# power_board.net
KiCad netlist of a schematic drawn in Altium Designer
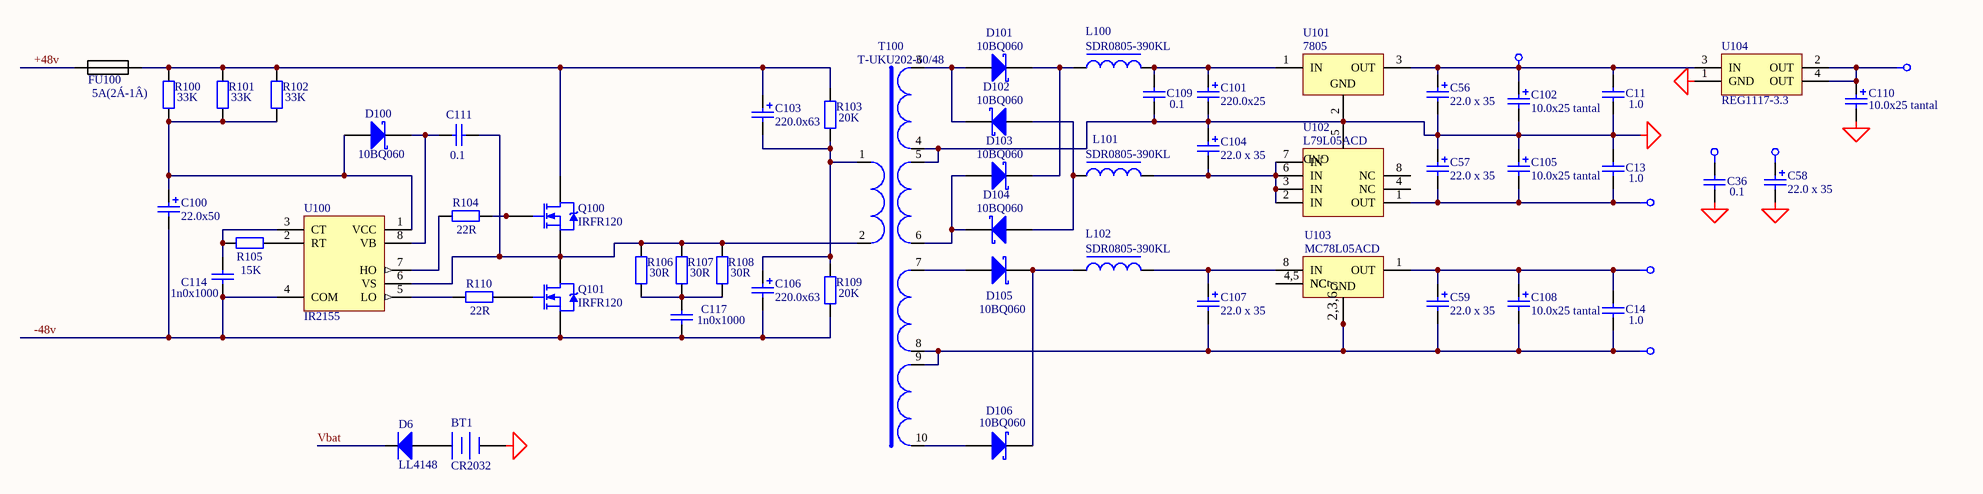
[diagram p0: power_board.SchDoc]

(export (version "E")
  (design (tool "Eeschema 10.0.6"))
  (components
    (comp (ref "BT1")
      (value "CR2032")
      (footprint "BAT_SUPP")
      (description "Multicell Battery")
      (fields (field (name "MANUFACTURER") "Generic Components") (field (name "PUBLISHER") "Altium Limited"))
      (libsource (lib "Miscellaneous Devices") (part "Battery"))
    )
    (comp (ref "C11")
      (value "1.0")
      (footprint "C3216-1206")
      (description "Capacitor (Semiconductor SIM Model)")
      (fields (field (name "MANUFACTURER") "Generic Components") (field (name "PUBLISHER") "Altium Limited"))
      (libsource (lib "Miscellaneous Devices") (part "Cap Semi"))
    )
    (comp (ref "C13")
      (value "1.0")
      (footprint "C3216-1206")
      (description "Capacitor (Semiconductor SIM Model)")
      (fields (field (name "MANUFACTURER") "Generic Components") (field (name "PUBLISHER") "Altium Limited"))
      (libsource (lib "Miscellaneous Devices") (part "Cap Semi"))
    )
    (comp (ref "C14")
      (value "1.0")
      (footprint "C3216-1206")
      (description "Capacitor (Semiconductor SIM Model)")
      (fields (field (name "MANUFACTURER") "Generic Components") (field (name "PUBLISHER") "Altium Limited"))
      (libsource (lib "Miscellaneous Devices") (part "Cap Semi"))
    )
    (comp (ref "C36")
      (value "0.1")
      (footprint "C3216-1206")
      (description "Capacitor (Semiconductor SIM Model)")
      (fields (field (name "MANUFACTURER") "Generic Components") (field (name "PUBLISHER") "Altium Limited"))
      (libsource (lib "Miscellaneous Devices") (part "Cap Semi"))
    )
    (comp (ref "C56")
      (value "22.0 x 35")
      (footprint "el3")
      (description "Polarized Capacitor (Radial)")
      (fields (field (name "MANUFACTURER") "Generic Components") (field (name "PUBLISHER") "Altium Limited"))
      (libsource (lib "PAL") (part "Cap Pol1"))
    )
    (comp (ref "C57")
      (value "22.0 x 35")
      (footprint "el3")
      (description "Polarized Capacitor (Radial)")
      (fields (field (name "MANUFACTURER") "Generic Components") (field (name "PUBLISHER") "Altium Limited"))
      (libsource (lib "PAL") (part "Cap Pol1"))
    )
    (comp (ref "C58")
      (value "22.0 x 35")
      (footprint "el3")
      (description "Polarized Capacitor (Radial)")
      (fields (field (name "MANUFACTURER") "Generic Components") (field (name "PUBLISHER") "Altium Limited"))
      (libsource (lib "PAL") (part "Cap Pol1"))
    )
    (comp (ref "C59")
      (value "22.0 x 35")
      (footprint "el3")
      (description "Polarized Capacitor (Radial)")
      (fields (field (name "MANUFACTURER") "Generic Components") (field (name "PUBLISHER") "Altium Limited"))
      (libsource (lib "PAL") (part "Cap Pol1"))
    )
    (comp (ref "C100")
      (value "22.0x50")
      (footprint "el3")
      (description "Polarized Capacitor (Radial)")
      (fields (field (name "MANUFACTURER") "Generic Components") (field (name "PUBLISHER") "Altium Limited"))
      (libsource (lib "PAL") (part "Cap Pol1"))
    )
    (comp (ref "C101")
      (value "220.0x25")
      (footprint "el5")
      (description "Polarized Capacitor (Radial)")
      (fields (field (name "MANUFACTURER") "Generic Components") (field (name "PUBLISHER") "Altium Limited"))
      (libsource (lib "PAL") (part "Cap Pol1"))
    )
    (comp (ref "C102")
      (value "10.0x25 tantal")
      (footprint "CAP_EL_6_3")
      (description "Polarized Capacitor (Radial)")
      (fields (field (name "MANUFACTURER") "Generic Components") (field (name "PUBLISHER") "Altium Limited"))
      (libsource (lib "PAL") (part "Cap Pol1"))
    )
    (comp (ref "C103")
      (value "220.0x63")
      (footprint "el5")
      (description "Polarized Capacitor (Radial)")
      (fields (field (name "MANUFACTURER") "Generic Components") (field (name "PUBLISHER") "Altium Limited"))
      (libsource (lib "PAL") (part "Cap Pol1"))
    )
    (comp (ref "C104")
      (value "22.0 x 35")
      (footprint "el3")
      (description "Polarized Capacitor (Radial)")
      (fields (field (name "MANUFACTURER") "Generic Components") (field (name "PUBLISHER") "Altium Limited"))
      (libsource (lib "PAL") (part "Cap Pol1"))
    )
    (comp (ref "C105")
      (value "10.0x25 tantal")
      (footprint "CAP_EL_6_3")
      (description "Polarized Capacitor (Radial)")
      (fields (field (name "MANUFACTURER") "Generic Components") (field (name "PUBLISHER") "Altium Limited"))
      (libsource (lib "PAL") (part "Cap Pol1"))
    )
    (comp (ref "C106")
      (value "220.0x63")
      (footprint "el5")
      (description "Polarized Capacitor (Radial)")
      (fields (field (name "MANUFACTURER") "Generic Components") (field (name "PUBLISHER") "Altium Limited"))
      (libsource (lib "PAL") (part "Cap Pol1"))
    )
    (comp (ref "C107")
      (value "22.0 x 35")
      (footprint "el3")
      (description "Polarized Capacitor (Radial)")
      (fields (field (name "MANUFACTURER") "Generic Components") (field (name "PUBLISHER") "Altium Limited"))
      (libsource (lib "PAL") (part "Cap Pol1"))
    )
    (comp (ref "C108")
      (value "10.0x25 tantal")
      (footprint "CAP_EL_6_3")
      (description "Polarized Capacitor (Radial)")
      (fields (field (name "MANUFACTURER") "Generic Components") (field (name "PUBLISHER") "Altium Limited"))
      (libsource (lib "PAL") (part "Cap Pol1"))
    )
    (comp (ref "C109")
      (value "0.1")
      (footprint "C3216-1206")
      (description "Capacitor (Semiconductor SIM Model)")
      (fields (field (name "MANUFACTURER") "Generic Components") (field (name "PUBLISHER") "Altium Limited"))
      (libsource (lib "Miscellaneous Devices") (part "Cap Semi"))
    )
    (comp (ref "C110")
      (value "10.0x25 tantal")
      (footprint "CAP_EL_6_3")
      (description "Polarized Capacitor (Radial)")
      (fields (field (name "MANUFACTURER") "Generic Components") (field (name "PUBLISHER") "Altium Limited"))
      (libsource (lib "PAL") (part "Cap Pol1"))
    )
    (comp (ref "C111")
      (value "0.1")
      (footprint "C3216-1206")
      (description "Capacitor (Semiconductor SIM Model)")
      (fields (field (name "MANUFACTURER") "Generic Components") (field (name "PUBLISHER") "Altium Limited"))
      (libsource (lib "Miscellaneous Devices") (part "Cap Semi"))
    )
    (comp (ref "C114")
      (value "1n0x1000")
      (footprint "_1206")
      (description "Capacitor (Semiconductor SIM Model)")
      (fields (field (name "MANUFACTURER") "Generic Components") (field (name "PUBLISHER") "Altium Limited"))
      (libsource (lib "Miscellaneous Devices") (part "Cap Semi"))
    )
    (comp (ref "C117")
      (value "1n0x1000")
      (footprint "_1206")
      (description "Capacitor (Semiconductor SIM Model)")
      (fields (field (name "MANUFACTURER") "Generic Components") (field (name "PUBLISHER") "Altium Limited"))
      (libsource (lib "Miscellaneous Devices") (part "Cap Semi"))
    )
    (comp (ref "D6")
      (value "LL4148")
      (footprint "_1206d")
      (description "Default Diode")
      (fields (field (name "MANUFACTURER") "Generic Components") (field (name "PUBLISHER") "Altium Limited"))
      (libsource (lib "PAL") (part "Diode"))
    )
    (comp (ref "D100")
      (value "10BQ060")
      (footprint "D_6_3")
      (description "Schottky Rectifier")
      (fields
        (field (name "MANUFACTURER") "International Rectifier")
        (field (name "PUBLISHER") "Altium Limited")
      )
      (libsource (lib "IR Discrete Diode") (part "10BQ015"))
    )
    (comp (ref "D101")
      (value "10BQ060")
      (footprint "D_6_3")
      (description "Schottky Rectifier")
      (fields
        (field (name "MANUFACTURER") "International Rectifier")
        (field (name "PUBLISHER") "Altium Limited")
      )
      (libsource (lib "IR Discrete Diode") (part "10BQ015"))
    )
    (comp (ref "D102")
      (value "10BQ060")
      (footprint "D_6_3")
      (description "Schottky Rectifier")
      (fields
        (field (name "MANUFACTURER") "International Rectifier")
        (field (name "PUBLISHER") "Altium Limited")
      )
      (libsource (lib "IR Discrete Diode") (part "10BQ015"))
    )
    (comp (ref "D103")
      (value "10BQ060")
      (footprint "D_6_3")
      (description "Schottky Rectifier")
      (fields
        (field (name "MANUFACTURER") "International Rectifier")
        (field (name "PUBLISHER") "Altium Limited")
      )
      (libsource (lib "IR Discrete Diode") (part "10BQ015"))
    )
    (comp (ref "D104")
      (value "10BQ060")
      (footprint "D_6_3")
      (description "Schottky Rectifier")
      (fields
        (field (name "MANUFACTURER") "International Rectifier")
        (field (name "PUBLISHER") "Altium Limited")
      )
      (libsource (lib "IR Discrete Diode") (part "10BQ015"))
    )
    (comp (ref "D105")
      (value "10BQ060")
      (footprint "D_6_3")
      (description "Schottky Rectifier")
      (fields
        (field (name "MANUFACTURER") "International Rectifier")
        (field (name "PUBLISHER") "Altium Limited")
      )
      (libsource (lib "IR Discrete Diode") (part "10BQ015"))
    )
    (comp (ref "D106")
      (value "10BQ060")
      (footprint "D_6_3")
      (description "Schottky Rectifier")
      (fields
        (field (name "MANUFACTURER") "International Rectifier")
        (field (name "PUBLISHER") "Altium Limited")
      )
      (libsource (lib "IR Discrete Diode") (part "10BQ015"))
    )
    (comp (ref "FU100") (value "5A(2Á-1Â)") (footprint "FUSE2") (libsource (lib "PAL") (part "FUSE")))
    (comp (ref "L100")
      (value "SDR0805-390KL")
      (footprint "L10x10")
      (description "Magnetic-Core Inductor")
      (fields (field (name "MANUFACTURER") "Generic Components") (field (name "PUBLISHER") "Altium Limited"))
      (libsource (lib "PAL") (part "Inductor Konstr 2"))
    )
    (comp (ref "L101")
      (value "SDR0805-390KL")
      (footprint "L10x10")
      (description "Magnetic-Core Inductor")
      (fields (field (name "MANUFACTURER") "Generic Components") (field (name "PUBLISHER") "Altium Limited"))
      (libsource (lib "PAL") (part "Inductor Konstr 2"))
    )
    (comp (ref "L102")
      (value "SDR0805-390KL")
      (footprint "L10x10")
      (description "Magnetic-Core Inductor")
      (fields (field (name "MANUFACTURER") "Generic Components") (field (name "PUBLISHER") "Altium Limited"))
      (libsource (lib "PAL") (part "Inductor Konstr 2"))
    )
    (comp (ref "Q100")
      (value "IRFR120")
      (footprint "SIP-G3/E8")
      (description "HEXFET N-Channel Power MOSFET")
      (fields
        (field (name "MANUFACTURER") "International Rectifier")
        (field (name "PUBLISHER") "Altium Limited")
      )
      (libsource (lib "IR Discrete MOSFET") (part "IRFR120"))
    )
    (comp (ref "Q101")
      (value "IRFR120")
      (footprint "SIP-G3/E8")
      (description "HEXFET N-Channel Power MOSFET")
      (fields
        (field (name "MANUFACTURER") "International Rectifier")
        (field (name "PUBLISHER") "Altium Limited")
      )
      (libsource (lib "IR Discrete MOSFET") (part "IRFR120"))
    )
    (comp (ref "R100")
      (value "33K")
      (footprint "_1206")
      (description "Resistor")
      (fields (field (name "MANUFACTURER") "Generic Components") (field (name "PUBLISHER") "Altium Limited"))
      (libsource (lib "") (part "Res2_1"))
    )
    (comp (ref "R101")
      (value "33K")
      (footprint "_1206")
      (description "Resistor")
      (fields (field (name "MANUFACTURER") "Generic Components") (field (name "PUBLISHER") "Altium Limited"))
      (libsource (lib "") (part "Res2_1"))
    )
    (comp (ref "R102")
      (value "33K")
      (footprint "_1206")
      (description "Resistor")
      (fields (field (name "MANUFACTURER") "Generic Components") (field (name "PUBLISHER") "Altium Limited"))
      (libsource (lib "") (part "Res2_1"))
    )
    (comp (ref "R103")
      (value "20K")
      (footprint "_1206")
      (description "Resistor")
      (fields (field (name "MANUFACTURER") "Generic Components") (field (name "PUBLISHER") "Altium Limited"))
      (libsource (lib "") (part "Res2_1"))
    )
    (comp (ref "R104")
      (value "22R")
      (footprint "_1206")
      (description "Resistor")
      (fields (field (name "MANUFACTURER") "Generic Components") (field (name "PUBLISHER") "Altium Limited"))
      (libsource (lib "Miscellaneous Devices") (part "Res2"))
    )
    (comp (ref "R105")
      (value "15K")
      (footprint "_1206")
      (description "Resistor")
      (fields (field (name "MANUFACTURER") "Generic Components") (field (name "PUBLISHER") "Altium Limited"))
      (libsource (lib "Miscellaneous Devices") (part "Res2"))
    )
    (comp (ref "R106")
      (value "30R")
      (footprint "_1206")
      (description "Resistor")
      (fields (field (name "MANUFACTURER") "Generic Components") (field (name "PUBLISHER") "Altium Limited"))
      (libsource (lib "") (part "Res2_1"))
    )
    (comp (ref "R107")
      (value "30R")
      (footprint "_1206")
      (description "Resistor")
      (fields (field (name "MANUFACTURER") "Generic Components") (field (name "PUBLISHER") "Altium Limited"))
      (libsource (lib "") (part "Res2_1"))
    )
    (comp (ref "R108")
      (value "30R")
      (footprint "_1206")
      (description "Resistor")
      (fields (field (name "MANUFACTURER") "Generic Components") (field (name "PUBLISHER") "Altium Limited"))
      (libsource (lib "") (part "Res2_1"))
    )
    (comp (ref "R109")
      (value "20K")
      (footprint "_1206")
      (description "Resistor")
      (fields (field (name "MANUFACTURER") "Generic Components") (field (name "PUBLISHER") "Altium Limited"))
      (libsource (lib "") (part "Res2_1"))
    )
    (comp (ref "R110")
      (value "22R")
      (footprint "_1206")
      (description "Resistor")
      (fields (field (name "MANUFACTURER") "Generic Components") (field (name "PUBLISHER") "Altium Limited"))
      (libsource (lib "Miscellaneous Devices") (part "Res2"))
    )
    (comp (ref "T100")
      (value "T-UKU202-60/48")
      (footprint "trans_ring1")
      (libsource (lib "PAL") (part "TRANS_RING1"))
    )
    (comp (ref "U100")
      (value "IR2155")
      (footprint "DIP-8/D11")
      (description "Self-Oscillating Half-Bridge Driver")
      (fields
        (field (name "MANUFACTURER") "International Rectifier")
        (field (name "PUBLISHER") "Altium Limited")
      )
      (libsource (lib "IR Interface Bridge Driver") (part "IR2155"))
    )
    (comp (ref "U101")
      (value "7805")
      (footprint "D2PAK")
      (description "3-Terminal Positive Fixed Voltage Regulator")
      (fields (field (name "MANUFACTURER") "Motorola") (field (name "PUBLISHER") "Altium Limited"))
      (libsource (lib "PAL") (part "7805"))
    )
    (comp (ref "U102")
      (value "L79L05ACD")
      (footprint "SO-G8")
      (description "Negative Voltage Regulator")
      (fields (field (name "MANUFACTURER") "ST-Microelectronics") (field (name "PUBLISHER") "Altium Limited"))
      (libsource (lib "ST Power Mgt Voltage Regulator") (part "L79L05ACD"))
    )
    (comp (ref "U103")
      (value "MC78L05ACD")
      (footprint "SO-G8")
      (description "3-Terminal Low-Current Positive Fixed Voltage Regulator")
      (fields (field (name "MANUFACTURER") "Motorola") (field (name "PUBLISHER") "Altium Limited"))
      (libsource (lib "Motorola Power Management Voltage Regulator") (part "MC78L05ACD"))
    )
    (comp (ref "U104")
      (value "REG1117-3.3")
      (footprint "SIP-G3/C7.4")
      (description "800mA and 1A Low Dropout Positive Regulator 2.85V, 3.3V, 5V, and Adjustable")
      (fields (field (name "MANUFACTURER") "Burr-Brown") (field (name "PUBLISHER") "Altium Limited"))
      (libsource (lib "BB Power Mgt Voltage Regulator") (part "REG1117-3.3"))
    )
  )
  (nets
    (net (code "1") (name "+3v3") (class "Default")
      (node (ref "C110") (pin "1") (pinfunction "1_1") (pintype "passive"))
      (node (ref "C36") (pin "2") (pinfunction "2_2") (pintype "passive"))
      (node (ref "C58") (pin "1") (pinfunction "1_1") (pintype "passive"))
      (node (ref "U104") (pin "2") (pinfunction "OUT_2") (pintype "power_in"))
      (node (ref "U104") (pin "4") (pinfunction "OUT_4") (pintype "power_in"))
    )
    (net (code "2") (name "+5v") (class "Default")
      (node (ref "C102") (pin "1") (pinfunction "1_1") (pintype "passive"))
      (node (ref "C11") (pin "2") (pinfunction "2_2") (pintype "passive"))
      (node (ref "C56") (pin "1") (pinfunction "1_1") (pintype "passive"))
      (node (ref "U101") (pin "3") (pinfunction "OUT_3") (pintype "power_in"))
      (node (ref "U104") (pin "3") (pinfunction "IN_3") (pintype "power_in"))
    )
    (net (code "3") (name "+5viz") (class "Default")
      (node (ref "C108") (pin "1") (pinfunction "1_1") (pintype "passive"))
      (node (ref "C14") (pin "2") (pinfunction "2_2") (pintype "passive"))
      (node (ref "C59") (pin "1") (pinfunction "1_1") (pintype "passive"))
      (node (ref "U103") (pin "1") (pinfunction "OUT_1") (pintype "power_in"))
    )
    (net (code "4") (name "-5v") (class "Default")
      (node (ref "C105") (pin "2") (pinfunction "2_2") (pintype "passive"))
      (node (ref "C13") (pin "1") (pinfunction "1_1") (pintype "passive"))
      (node (ref "C57") (pin "2") (pinfunction "2_2") (pintype "passive"))
      (node (ref "U102") (pin "1") (pinfunction "OUT_1") (pintype "power_in"))
    )
    (net (code "5") (name "-5viz") (class "Default")
      (node (ref "C107") (pin "2") (pinfunction "2_2") (pintype "passive"))
      (node (ref "C108") (pin "2") (pinfunction "2_2") (pintype "passive"))
      (node (ref "C14") (pin "1") (pinfunction "1_1") (pintype "passive"))
      (node (ref "C59") (pin "2") (pinfunction "2_2") (pintype "passive"))
      (node (ref "T100") (pin "8") (pinfunction "Vss_8") (pintype "passive"))
      (node (ref "T100") (pin "9") (pinfunction "Vss_9") (pintype "passive"))
      (node (ref "U103") (pin "2") (pinfunction "GND_2") (pintype "power_in"))
      (node (ref "U103") (pin "3") (pinfunction "GND_3") (pintype "power_in"))
      (node (ref "U103") (pin "6") (pinfunction "GND_6") (pintype "power_in"))
      (node (ref "U103") (pin "7") (pinfunction "GND_7") (pintype "power_in"))
    )
    (net (code "6") (name "/+48v") (class "Default")
      (node (ref "FU100") (pin "1") (pinfunction "1_1") (pintype "passive"))
    )
    (net (code "7") (name "/-48v") (class "Default")
      (node (ref "C100") (pin "2") (pinfunction "2_2") (pintype "passive"))
      (node (ref "C106") (pin "2") (pinfunction "2_2") (pintype "passive"))
      (node (ref "C114") (pin "2") (pinfunction "2_2") (pintype "passive"))
      (node (ref "C117") (pin "2") (pinfunction "2_2") (pintype "passive"))
      (node (ref "Q101") (pin "3") (pinfunction "S_3") (pintype "passive"))
      (node (ref "R109") (pin "2") (pinfunction "2_2") (pintype "passive"))
      (node (ref "U100") (pin "4") (pinfunction "COM_4") (pintype "power_in"))
    )
    (net (code "8") (name "/Vbat") (class "Default")
      (node (ref "D6") (pin "2") (pinfunction "K_2") (pintype "passive"))
    )
    (net (code "9") (name "GND") (class "Default")
      (node (ref "BT1") (pin "2") (pinfunction "-_2") (pintype "passive"))
      (node (ref "C101") (pin "2") (pinfunction "2_2") (pintype "passive"))
      (node (ref "C102") (pin "2") (pinfunction "2_2") (pintype "passive"))
      (node (ref "C104") (pin "1") (pinfunction "1_1") (pintype "passive"))
      (node (ref "C105") (pin "1") (pinfunction "1_1") (pintype "passive"))
      (node (ref "C109") (pin "1") (pinfunction "1_1") (pintype "passive"))
      (node (ref "C11") (pin "1") (pinfunction "1_1") (pintype "passive"))
      (node (ref "C110") (pin "2") (pinfunction "2_2") (pintype "passive"))
      (node (ref "C13") (pin "2") (pinfunction "2_2") (pintype "passive"))
      (node (ref "C36") (pin "1") (pinfunction "1_1") (pintype "passive"))
      (node (ref "C56") (pin "2") (pinfunction "2_2") (pintype "passive"))
      (node (ref "C57") (pin "1") (pinfunction "1_1") (pintype "passive"))
      (node (ref "C58") (pin "2") (pinfunction "2_2") (pintype "passive"))
      (node (ref "T100") (pin "4") (pinfunction "Vss_4") (pintype "passive"))
      (node (ref "T100") (pin "5") (pinfunction "Vss_5") (pintype "passive"))
      (node (ref "U101") (pin "2") (pinfunction "GND_2") (pintype "power_in"))
      (node (ref "U102") (pin "5") (pinfunction "GND_5") (pintype "power_in"))
      (node (ref "U104") (pin "1") (pinfunction "GND_1") (pintype "power_in"))
    )
    (net (code "10") (name "Net-(BT1-+)") (class "Default")
      (node (ref "BT1") (pin "1") (pinfunction "+_1") (pintype "passive"))
      (node (ref "D6") (pin "1") (pinfunction "A_1") (pintype "passive"))
    )
    (net (code "11") (name "Net-(C103-Pad2)") (class "Default")
      (node (ref "C103") (pin "2") (pinfunction "2_2") (pintype "passive"))
      (node (ref "C106") (pin "1") (pinfunction "1_1") (pintype "passive"))
      (node (ref "R103") (pin "2") (pinfunction "2_2") (pintype "passive"))
      (node (ref "R109") (pin "1") (pinfunction "1_1") (pintype "passive"))
      (node (ref "T100") (pin "1") (pinfunction "Vss_1") (pintype "passive"))
    )
    (net (code "12") (name "Net-(C104-Pad2)") (class "Default")
      (node (ref "C104") (pin "2") (pinfunction "2_2") (pintype "passive"))
      (node (ref "L101") (pin "2") (pinfunction "2_2") (pintype "passive"))
      (node (ref "U102") (pin "2") (pinfunction "IN_2") (pintype "power_in"))
      (node (ref "U102") (pin "3") (pinfunction "IN_3") (pintype "power_in"))
      (node (ref "U102") (pin "6") (pinfunction "IN_6") (pintype "power_in"))
      (node (ref "U102") (pin "7") (pinfunction "IN_7") (pintype "power_in"))
    )
    (net (code "13") (name "Net-(C117-Pad1)") (class "Default")
      (node (ref "C117") (pin "1") (pinfunction "1_1") (pintype "passive"))
      (node (ref "R106") (pin "2") (pinfunction "2_2") (pintype "passive"))
      (node (ref "R107") (pin "2") (pinfunction "2_2") (pintype "passive"))
      (node (ref "R108") (pin "2") (pinfunction "2_2") (pintype "passive"))
    )
    (net (code "14") (name "Net-(D100-A)") (class "Default")
      (node (ref "C100") (pin "1") (pinfunction "1_1") (pintype "passive"))
      (node (ref "D100") (pin "1") (pinfunction "A_1") (pintype "passive"))
      (node (ref "R100") (pin "2") (pinfunction "2_2") (pintype "passive"))
      (node (ref "R101") (pin "2") (pinfunction "2_2") (pintype "passive"))
      (node (ref "R102") (pin "2") (pinfunction "2_2") (pintype "passive"))
      (node (ref "U100") (pin "1") (pinfunction "VCC_1") (pintype "power_in"))
    )
    (net (code "15") (name "Net-(D100-K)") (class "Default")
      (node (ref "C111") (pin "1") (pinfunction "1_1") (pintype "passive"))
      (node (ref "D100") (pin "2") (pinfunction "K_2") (pintype "passive"))
      (node (ref "U100") (pin "8") (pinfunction "VB_8") (pintype "power_in"))
    )
    (net (code "16") (name "Net-(D101-A)") (class "Default")
      (node (ref "D101") (pin "1") (pinfunction "A_1") (pintype "passive"))
      (node (ref "D102") (pin "2") (pinfunction "K_2") (pintype "passive"))
      (node (ref "T100") (pin "3") (pinfunction "Vss_3") (pintype "passive"))
    )
    (net (code "17") (name "Net-(D101-K)") (class "Default")
      (node (ref "D101") (pin "2") (pinfunction "K_2") (pintype "passive"))
      (node (ref "D103") (pin "2") (pinfunction "K_2") (pintype "passive"))
      (node (ref "L100") (pin "1") (pinfunction "1_1") (pintype "passive"))
    )
    (net (code "18") (name "Net-(D102-A)") (class "Default")
      (node (ref "D102") (pin "1") (pinfunction "A_1") (pintype "passive"))
      (node (ref "D104") (pin "1") (pinfunction "A_1") (pintype "passive"))
      (node (ref "L101") (pin "1") (pinfunction "1_1") (pintype "passive"))
    )
    (net (code "19") (name "Net-(D103-A)") (class "Default")
      (node (ref "D103") (pin "1") (pinfunction "A_1") (pintype "passive"))
      (node (ref "D104") (pin "2") (pinfunction "K_2") (pintype "passive"))
      (node (ref "T100") (pin "6") (pinfunction "Vss_6") (pintype "passive"))
    )
    (net (code "20") (name "Net-(D105-A)") (class "Default")
      (node (ref "D105") (pin "1") (pinfunction "A_1") (pintype "passive"))
      (node (ref "T100") (pin "7") (pinfunction "Vss_7") (pintype "passive"))
    )
    (net (code "21") (name "Net-(D105-K)") (class "Default")
      (node (ref "D105") (pin "2") (pinfunction "K_2") (pintype "passive"))
      (node (ref "D106") (pin "2") (pinfunction "K_2") (pintype "passive"))
      (node (ref "L102") (pin "1") (pinfunction "1_1") (pintype "passive"))
    )
    (net (code "22") (name "Net-(D106-A)") (class "Default")
      (node (ref "D106") (pin "1") (pinfunction "A_1") (pintype "passive"))
      (node (ref "T100") (pin "10") (pinfunction "Vss_10") (pintype "passive"))
    )
    (net (code "23") (name "Net-(Q100-D)") (class "Default")
      (node (ref "C103") (pin "1") (pinfunction "1_1") (pintype "passive"))
      (node (ref "FU100") (pin "2") (pinfunction "2_2") (pintype "passive"))
      (node (ref "Q100") (pin "4") (pinfunction "D_4") (pintype "passive"))
      (node (ref "R100") (pin "1") (pinfunction "1_1") (pintype "passive"))
      (node (ref "R101") (pin "1") (pinfunction "1_1") (pintype "passive"))
      (node (ref "R102") (pin "1") (pinfunction "1_1") (pintype "passive"))
      (node (ref "R103") (pin "1") (pinfunction "1_1") (pintype "passive"))
    )
    (net (code "24") (name "Net-(Q100-G)") (class "Default")
      (node (ref "Q100") (pin "1") (pinfunction "G_1") (pintype "passive"))
      (node (ref "R104") (pin "2") (pinfunction "2_2") (pintype "passive"))
    )
    (net (code "25") (name "Net-(Q100-S)") (class "Default")
      (node (ref "C111") (pin "2") (pinfunction "2_2") (pintype "passive"))
      (node (ref "Q100") (pin "3") (pinfunction "S_3") (pintype "passive"))
      (node (ref "Q101") (pin "4") (pinfunction "D_4") (pintype "passive"))
      (node (ref "R106") (pin "1") (pinfunction "1_1") (pintype "passive"))
      (node (ref "R107") (pin "1") (pinfunction "1_1") (pintype "passive"))
      (node (ref "R108") (pin "1") (pinfunction "1_1") (pintype "passive"))
      (node (ref "T100") (pin "2") (pinfunction "Vss_2") (pintype "passive"))
      (node (ref "U100") (pin "6") (pinfunction "VS_6") (pintype "power_in"))
    )
    (net (code "26") (name "Net-(Q101-G)") (class "Default")
      (node (ref "Q101") (pin "1") (pinfunction "G_1") (pintype "passive"))
      (node (ref "R110") (pin "2") (pinfunction "2_2") (pintype "passive"))
    )
    (net (code "27") (name "Net-(U100-CT)") (class "Default")
      (node (ref "C114") (pin "1") (pinfunction "1_1") (pintype "passive"))
      (node (ref "R105") (pin "1") (pinfunction "1_1") (pintype "passive"))
      (node (ref "U100") (pin "3") (pinfunction "CT_3") (pintype "passive"))
    )
    (net (code "28") (name "Net-(U100-HO)") (class "Default")
      (node (ref "R104") (pin "1") (pinfunction "1_1") (pintype "passive"))
      (node (ref "U100") (pin "7") (pinfunction "HO_7") (pintype "output"))
    )
    (net (code "29") (name "Net-(U100-LO)") (class "Default")
      (node (ref "R110") (pin "1") (pinfunction "1_1") (pintype "passive"))
      (node (ref "U100") (pin "5") (pinfunction "LO_5") (pintype "output"))
    )
    (net (code "30") (name "Net-(U100-RT)") (class "Default")
      (node (ref "R105") (pin "2") (pinfunction "2_2") (pintype "passive"))
      (node (ref "U100") (pin "2") (pinfunction "RT_2") (pintype "passive"))
    )
    (net (code "31") (name "Net-(U101-IN)") (class "Default")
      (node (ref "C101") (pin "1") (pinfunction "1_1") (pintype "passive"))
      (node (ref "C109") (pin "2") (pinfunction "2_2") (pintype "passive"))
      (node (ref "L100") (pin "2") (pinfunction "2_2") (pintype "passive"))
      (node (ref "U101") (pin "1") (pinfunction "IN_1") (pintype "power_in"))
    )
    (net (code "32") (name "Net-(U103-IN)") (class "Default")
      (node (ref "C107") (pin "1") (pinfunction "1_1") (pintype "passive"))
      (node (ref "L102") (pin "2") (pinfunction "2_2") (pintype "passive"))
      (node (ref "U103") (pin "8") (pinfunction "IN_8") (pintype "power_in"))
    )
    (net (code "33") (name "Net-(U103-NC-Pad4)") (class "Default")
      (node (ref "U103") (pin "4") (pinfunction "NC_4") (pintype "passive"))
      (node (ref "U103") (pin "5") (pinfunction "NC_5") (pintype "passive"))
    )
    (net (code "34") (name "unconnected-(U102-NC-Pad4)") (class "Default")
      (node (ref "U102") (pin "4") (pinfunction "NC_4") (pintype "passive"))
    )
    (net (code "35") (name "unconnected-(U102-NC-Pad8)") (class "Default")
      (node (ref "U102") (pin "8") (pinfunction "NC_8") (pintype "passive"))
    )
  )
)
